# Nudge.net
KiCad netlist of a schematic drawn in EasyEDA Pro
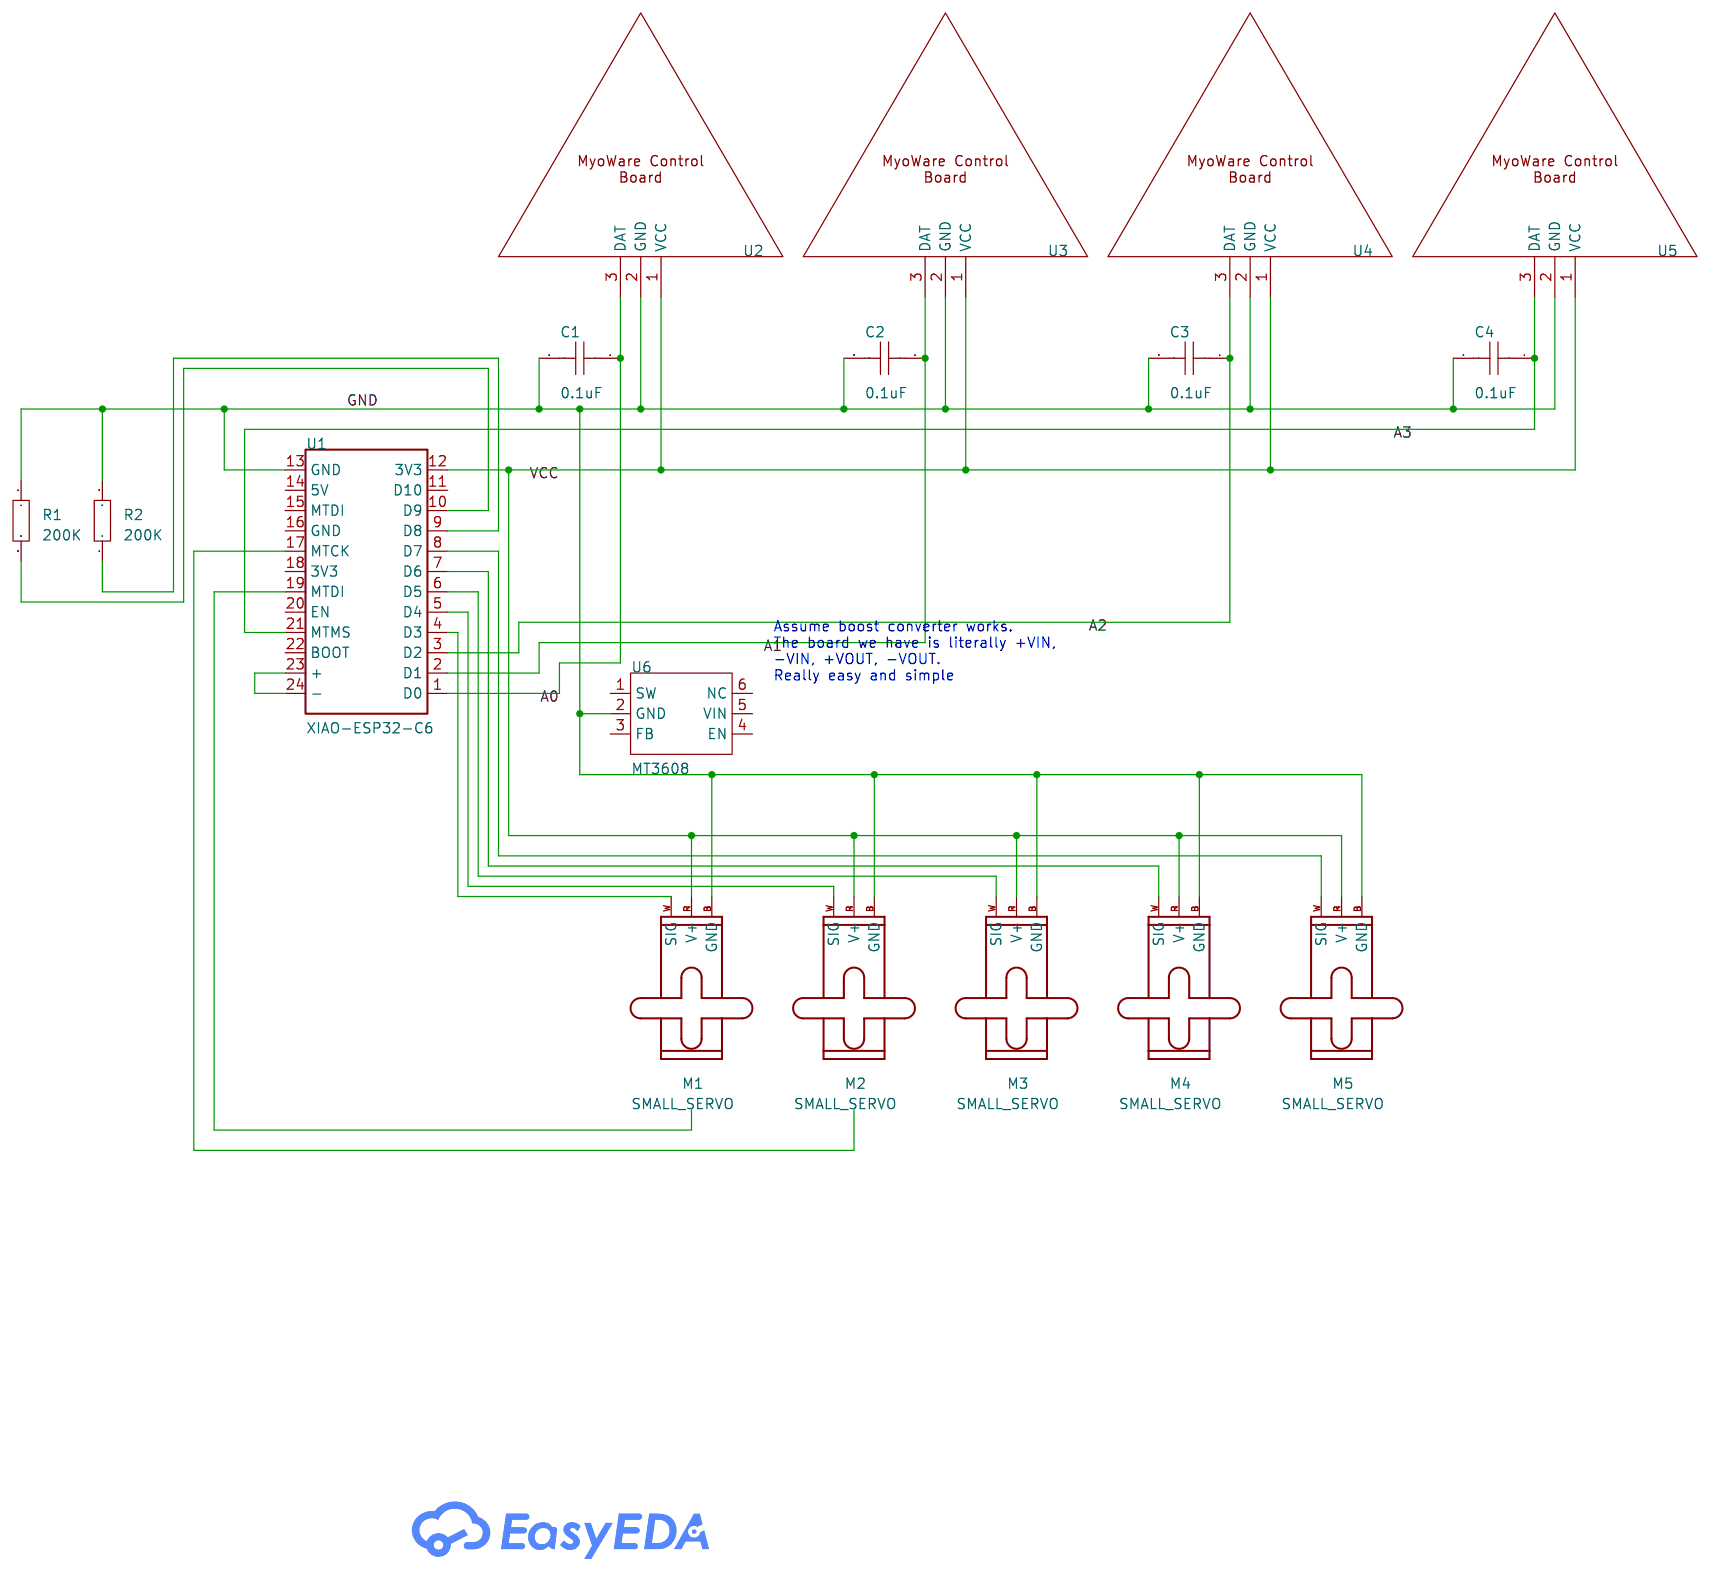
[diagram p0: schematic sheet]

(export (version "E")
  (design (tool "Eeschema 10.0.6"))
  (components
    (comp (ref "C1")
      (value "0.1uF")
      (footprint "easyedapro:C0603")
      (libsource (lib "easyedapro") (part "CapAcitance"))
    )
    (comp (ref "C2")
      (value "0.1uF")
      (footprint "easyedapro:C0603")
      (libsource (lib "easyedapro") (part "CapAcitance"))
    )
    (comp (ref "C3")
      (value "0.1uF")
      (footprint "easyedapro:C0603")
      (libsource (lib "easyedapro") (part "CapAcitance"))
    )
    (comp (ref "C4")
      (value "0.1uF")
      (footprint "easyedapro:C0603")
      (libsource (lib "easyedapro") (part "CapAcitance"))
    )
    (comp (ref "M1") (value "SMALL_SERVO") (libsource (lib "easyedapro") (part "SMALL_SERVO")))
    (comp (ref "M2") (value "SMALL_SERVO") (libsource (lib "easyedapro") (part "SMALL_SERVO")))
    (comp (ref "M3") (value "SMALL_SERVO") (libsource (lib "easyedapro") (part "SMALL_SERVO")))
    (comp (ref "M4") (value "SMALL_SERVO") (libsource (lib "easyedapro") (part "SMALL_SERVO")))
    (comp (ref "M5") (value "SMALL_SERVO") (libsource (lib "easyedapro") (part "SMALL_SERVO")))
    (comp (ref "R1")
      (value "200K")
      (footprint "easyedapro:R0603")
      (libsource (lib "easyedapro") (part "Res"))
    )
    (comp (ref "R2")
      (value "200K")
      (footprint "easyedapro:R0603")
      (libsource (lib "easyedapro") (part "Res"))
    )
    (comp (ref "U1") (value "XIAO-ESP32-C6") (libsource (lib "easyedapro") (part "XIAO-ESP32-C6")))
    (comp (ref "U2") (value "~") (libsource (lib "easyedapro") (part "MyoWare Board")))
    (comp (ref "U3") (value "~") (libsource (lib "easyedapro") (part "MyoWare Board")))
    (comp (ref "U4") (value "~") (libsource (lib "easyedapro") (part "MyoWare Board")))
    (comp (ref "U5") (value "~") (libsource (lib "easyedapro") (part "MyoWare Board")))
    (comp (ref "U6")
      (value "MT3608")
      (footprint "easyedapro:SOT-23-6_L2.9-W1.6-P0.95-LS2.8-BR")
      (fields (field (name "Manufacturer") "西安航天民芯"))
      (libsource (lib "easyedapro") (part "MT3608_C49339555"))
    )
  )
  (nets
    (net (code "1") (name "/A0") (class "Default")
      (node (ref "C1") (pin "1") (pinfunction "1_1") (pintype "input"))
      (node (ref "U1") (pin "1") (pinfunction "D0_1") (pintype "unspecified"))
      (node (ref "U2") (pin "3") (pinfunction "DAT_3") (pintype "input"))
    )
    (net (code "2") (name "/A1") (class "Default")
      (node (ref "C2") (pin "1") (pinfunction "1_1") (pintype "input"))
      (node (ref "U1") (pin "2") (pinfunction "D1_2") (pintype "unspecified"))
      (node (ref "U3") (pin "3") (pinfunction "DAT_3") (pintype "input"))
    )
    (net (code "3") (name "/A2") (class "Default")
      (node (ref "C3") (pin "1") (pinfunction "1_1") (pintype "input"))
      (node (ref "U1") (pin "3") (pinfunction "D2_3") (pintype "unspecified"))
      (node (ref "U4") (pin "3") (pinfunction "DAT_3") (pintype "input"))
    )
    (net (code "4") (name "/A3") (class "Default")
      (node (ref "C4") (pin "1") (pinfunction "1_1") (pintype "input"))
      (node (ref "U1") (pin "21") (pinfunction "MTMS_21") (pintype "unspecified"))
      (node (ref "U5") (pin "3") (pinfunction "DAT_3") (pintype "input"))
    )
    (net (code "5") (name "/GND") (class "Default")
      (node (ref "C1") (pin "2") (pinfunction "2_2") (pintype "input"))
      (node (ref "C2") (pin "2") (pinfunction "2_2") (pintype "input"))
      (node (ref "C3") (pin "2") (pinfunction "2_2") (pintype "input"))
      (node (ref "C4") (pin "2") (pinfunction "2_2") (pintype "input"))
      (node (ref "M1") (pin "3") (pinfunction "GND_3") (pintype "unspecified"))
      (node (ref "M2") (pin "3") (pinfunction "GND_3") (pintype "unspecified"))
      (node (ref "M3") (pin "3") (pinfunction "GND_3") (pintype "unspecified"))
      (node (ref "M4") (pin "3") (pinfunction "GND_3") (pintype "unspecified"))
      (node (ref "M5") (pin "3") (pinfunction "GND_3") (pintype "unspecified"))
      (node (ref "R1") (pin "1") (pinfunction "1_1") (pintype "input"))
      (node (ref "R2") (pin "2") (pinfunction "2_2") (pintype "input"))
      (node (ref "U1") (pin "13") (pinfunction "GND_13") (pintype "unspecified"))
      (node (ref "U2") (pin "2") (pinfunction "GND_2") (pintype "input"))
      (node (ref "U3") (pin "2") (pinfunction "GND_2") (pintype "input"))
      (node (ref "U4") (pin "2") (pinfunction "GND_2") (pintype "input"))
      (node (ref "U5") (pin "2") (pinfunction "GND_2") (pintype "input"))
      (node (ref "U6") (pin "2") (pinfunction "GND_2") (pintype "unspecified"))
    )
    (net (code "6") (name "/VCC") (class "Default")
      (node (ref "M1") (pin "2") (pinfunction "V+_2") (pintype "unspecified"))
      (node (ref "M2") (pin "2") (pinfunction "V+_2") (pintype "unspecified"))
      (node (ref "M3") (pin "2") (pinfunction "V+_2") (pintype "unspecified"))
      (node (ref "M4") (pin "2") (pinfunction "V+_2") (pintype "unspecified"))
      (node (ref "M5") (pin "2") (pinfunction "V+_2") (pintype "unspecified"))
      (node (ref "U1") (pin "12") (pinfunction "3V3_12") (pintype "unspecified"))
      (node (ref "U2") (pin "1") (pinfunction "VCC_1") (pintype "input"))
      (node (ref "U3") (pin "1") (pinfunction "VCC_1") (pintype "input"))
      (node (ref "U4") (pin "1") (pinfunction "VCC_1") (pintype "input"))
      (node (ref "U5") (pin "1") (pinfunction "VCC_1") (pintype "input"))
    )
    (net (code "7") (name "Net-(M1-SIG)") (class "Default")
      (node (ref "M1") (pin "1") (pinfunction "SIG_1") (pintype "unspecified"))
      (node (ref "U1") (pin "4") (pinfunction "D3_4") (pintype "unspecified"))
    )
    (net (code "8") (name "Net-(M2-SIG)") (class "Default")
      (node (ref "M2") (pin "1") (pinfunction "SIG_1") (pintype "unspecified"))
      (node (ref "U1") (pin "5") (pinfunction "D4_5") (pintype "unspecified"))
    )
    (net (code "9") (name "Net-(M3-SIG)") (class "Default")
      (node (ref "M3") (pin "1") (pinfunction "SIG_1") (pintype "unspecified"))
      (node (ref "U1") (pin "6") (pinfunction "D5_6") (pintype "unspecified"))
    )
    (net (code "10") (name "Net-(M4-SIG)") (class "Default")
      (node (ref "M4") (pin "1") (pinfunction "SIG_1") (pintype "unspecified"))
      (node (ref "U1") (pin "7") (pinfunction "D6_7") (pintype "unspecified"))
    )
    (net (code "11") (name "Net-(M5-SIG)") (class "Default")
      (node (ref "M5") (pin "1") (pinfunction "SIG_1") (pintype "unspecified"))
      (node (ref "U1") (pin "8") (pinfunction "D7_8") (pintype "unspecified"))
    )
    (net (code "12") (name "Net-(U1-+)") (class "Default")
      (node (ref "U1") (pin "23") (pinfunction "+_23") (pintype "unspecified"))
      (node (ref "U1") (pin "24") (pinfunction "-_24") (pintype "unspecified"))
    )
    (net (code "13") (name "Net-(U1-D8)") (class "Default")
      (node (ref "R2") (pin "1") (pinfunction "1_1") (pintype "input"))
      (node (ref "U1") (pin "9") (pinfunction "D8_9") (pintype "unspecified"))
    )
    (net (code "14") (name "Net-(U1-D9)") (class "Default")
      (node (ref "R1") (pin "2") (pinfunction "2_2") (pintype "input"))
      (node (ref "U1") (pin "10") (pinfunction "D9_10") (pintype "unspecified"))
    )
    (net (code "15") (name "unconnected-(U1-3V3-Pad18)") (class "Default")
      (node (ref "U1") (pin "18") (pinfunction "3V3_18") (pintype "unspecified"))
    )
    (net (code "16") (name "unconnected-(U1-5V-Pad14)") (class "Default")
      (node (ref "U1") (pin "14") (pinfunction "5V_14") (pintype "unspecified"))
    )
    (net (code "17") (name "unconnected-(U1-BOOT-Pad22)") (class "Default")
      (node (ref "U1") (pin "22") (pinfunction "BOOT_22") (pintype "unspecified"))
    )
    (net (code "18") (name "unconnected-(U1-D10-Pad11)") (class "Default")
      (node (ref "U1") (pin "11") (pinfunction "D10_11") (pintype "unspecified"))
    )
    (net (code "19") (name "unconnected-(U1-EN-Pad20)") (class "Default")
      (node (ref "U1") (pin "20") (pinfunction "EN_20") (pintype "unspecified"))
    )
    (net (code "20") (name "unconnected-(U1-GND-Pad16)") (class "Default")
      (node (ref "U1") (pin "16") (pinfunction "GND_16") (pintype "unspecified"))
    )
    (net (code "21") (name "unconnected-(U1-MTCK-Pad17)") (class "Default")
      (node (ref "U1") (pin "17") (pinfunction "MTCK_17") (pintype "unspecified"))
    )
    (net (code "22") (name "unconnected-(U1-MTDI-Pad15)") (class "Default")
      (node (ref "U1") (pin "15") (pinfunction "MTDI_15") (pintype "unspecified"))
    )
    (net (code "23") (name "unconnected-(U1-MTDI-Pad19)") (class "Default")
      (node (ref "U1") (pin "19") (pinfunction "MTDI_19") (pintype "unspecified"))
    )
    (net (code "24") (name "unconnected-(U6-EN-Pad4)") (class "Default")
      (node (ref "U6") (pin "4") (pinfunction "EN_4") (pintype "unspecified"))
    )
    (net (code "25") (name "unconnected-(U6-FB-Pad3)") (class "Default")
      (node (ref "U6") (pin "3") (pinfunction "FB_3") (pintype "unspecified"))
    )
    (net (code "26") (name "unconnected-(U6-NC-Pad6)") (class "Default")
      (node (ref "U6") (pin "6") (pinfunction "NC_6") (pintype "unspecified"))
    )
    (net (code "27") (name "unconnected-(U6-SW-Pad1)") (class "Default")
      (node (ref "U6") (pin "1") (pinfunction "SW_1") (pintype "unspecified"))
    )
    (net (code "28") (name "unconnected-(U6-VIN-Pad5)") (class "Default")
      (node (ref "U6") (pin "5") (pinfunction "VIN_5") (pintype "unspecified"))
    )
  )
)
